# Xmas_base_board.net
KiCad netlist of a schematic drawn in EAGLE
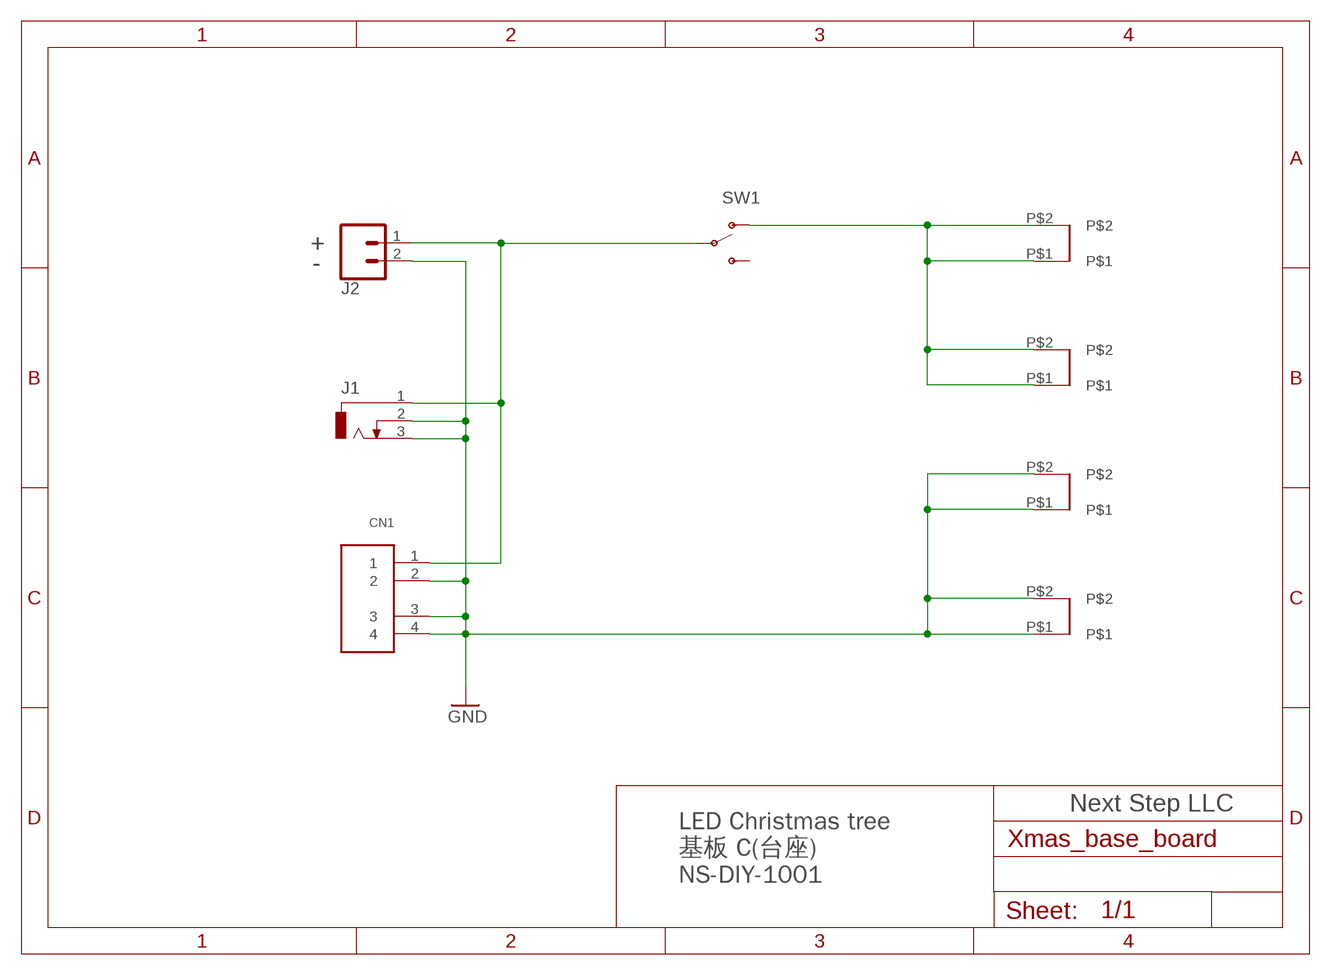
[diagram p0: schematic, sheet 1]

(export (version "E")
  (design (tool "Eeschema 10.0.6"))
  (components
    (comp (ref "CN1")
      (value "MRUSB-2B-D14NI-S306_MRUSB-2B")
      (footprint "eagle-import:MRUSB-2B-D14NI-S306_MRUSB-2B")
      (libsource (lib "eagle-import") (part "MRUSB-2B-D14NI-S306_MRUSB-2B"))
    )
    (comp (ref "J1")
      (value "DCJ0303")
      (footprint "eagle-import:DCJ0303")
      (libsource (lib "eagle-import") (part "DCJ0303"))
    )
    (comp (ref "J2")
      (value "CONN_02")
      (footprint "eagle-import:1X02")
      (libsource (lib "eagle-import") (part "CONN_02"))
    )
    (comp (ref "SW1")
      (value "SWITCH-SPDT-PTH-11.6X4.0MM")
      (footprint "eagle-import:SWITCH_SPDT_PTH_11.6X4.0MM")
      (libsource (lib "eagle-import") (part "SWITCH-SPDT-PTH-11.6X4.0MM"))
    )
    (comp (ref "U$5")
      (value "XMAS-TREE")
      (footprint "eagle-import:XMAS-TREE")
      (libsource (lib "eagle-import") (part "XMAS-TREE"))
    )
    (comp (ref "U$6")
      (value "XMAS-TREE")
      (footprint "eagle-import:XMAS-TREE")
      (libsource (lib "eagle-import") (part "XMAS-TREE"))
    )
    (comp (ref "U$7")
      (value "XMAS-TREE")
      (footprint "eagle-import:XMAS-TREE")
      (libsource (lib "eagle-import") (part "XMAS-TREE"))
    )
    (comp (ref "U$8")
      (value "XMAS-TREE")
      (footprint "eagle-import:XMAS-TREE")
      (libsource (lib "eagle-import") (part "XMAS-TREE"))
    )
  )
  (nets
    (net (code "1") (name "GND") (class "Default")
      (node (ref "CN1") (pin "2") (pinfunction "2_2") (pintype "bidirectional"))
      (node (ref "CN1") (pin "3") (pinfunction "3_3") (pintype "bidirectional"))
      (node (ref "CN1") (pin "4") (pinfunction "4_4") (pintype "bidirectional"))
      (node (ref "J1") (pin "2") (pinfunction "2_2") (pintype "passive"))
      (node (ref "J1") (pin "3") (pinfunction "3_3") (pintype "passive"))
      (node (ref "J2") (pin "2") (pinfunction "2_2") (pintype "passive"))
      (node (ref "U$7") (pin "P$1") (pinfunction "P$1_P$1") (pintype "bidirectional"))
      (node (ref "U$7") (pin "P$2") (pinfunction "P$2_P$2") (pintype "bidirectional"))
      (node (ref "U$8") (pin "P$1") (pinfunction "P$1_P$1") (pintype "bidirectional"))
      (node (ref "U$8") (pin "P$2") (pinfunction "P$2_P$2") (pintype "bidirectional"))
    )
    (net (code "2") (name "Net-(SW1-O)") (class "Default")
      (node (ref "SW1") (pin "1") (pinfunction "O_1") (pintype "passive"))
      (node (ref "U$5") (pin "P$1") (pinfunction "P$1_P$1") (pintype "bidirectional"))
      (node (ref "U$5") (pin "P$2") (pinfunction "P$2_P$2") (pintype "bidirectional"))
      (node (ref "U$6") (pin "P$1") (pinfunction "P$1_P$1") (pintype "bidirectional"))
      (node (ref "U$6") (pin "P$2") (pinfunction "P$2_P$2") (pintype "bidirectional"))
    )
    (net (code "3") (name "Net-(SW1-P)") (class "Default")
      (node (ref "CN1") (pin "1") (pinfunction "1_1") (pintype "bidirectional"))
      (node (ref "J1") (pin "1") (pinfunction "1_1") (pintype "passive"))
      (node (ref "J2") (pin "1") (pinfunction "1_1") (pintype "passive"))
      (node (ref "SW1") (pin "2") (pinfunction "P_2") (pintype "passive"))
    )
    (net (code "4") (name "unconnected-(SW1-S-Pad3)") (class "Default")
      (node (ref "SW1") (pin "3") (pinfunction "S_3") (pintype "passive"))
    )
  )
)
